# PiZeroRobotHat.net
KiCad netlist of a schematic drawn in EAGLE
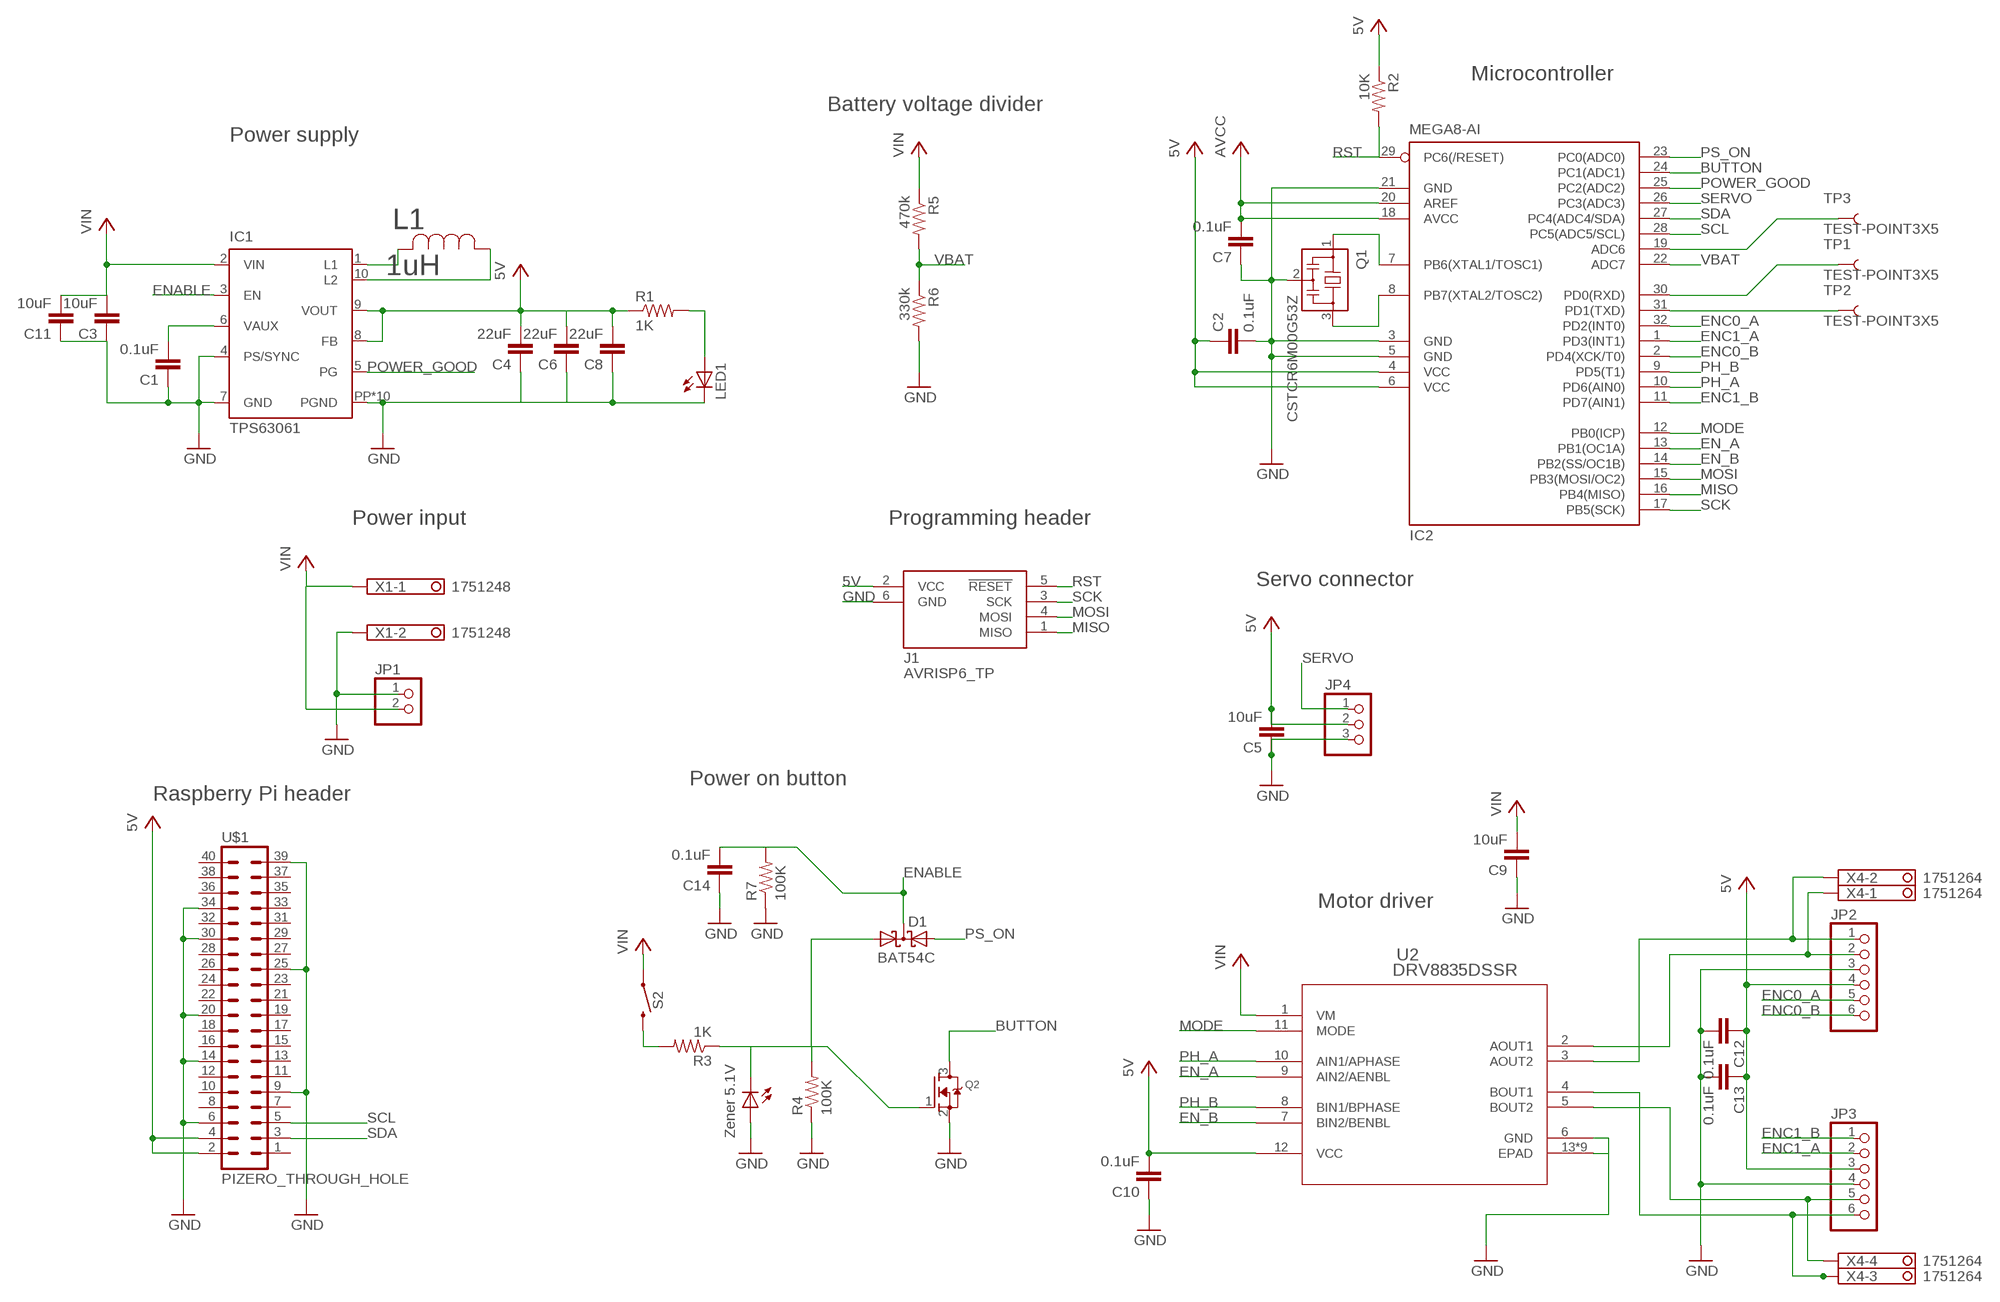
[diagram p0: schematic, sheet 1]

(export (version "E")
  (design (tool "Eeschema 10.0.6"))
  (components
    (comp (ref "C1")
      (value "0.1uF")
      (footprint "eagle-import:C0603K")
      (libsource (lib "eagle-import") (part "C-EUC0603K"))
    )
    (comp (ref "C2")
      (value "0.1uF")
      (footprint "eagle-import:C0603K")
      (libsource (lib "eagle-import") (part "C-EUC0603K"))
    )
    (comp (ref "C3")
      (value "10uF")
      (footprint "eagle-import:C0805K")
      (libsource (lib "eagle-import") (part "C-EUC0805K"))
    )
    (comp (ref "C4")
      (value "22uF")
      (footprint "eagle-import:C0805K")
      (libsource (lib "eagle-import") (part "C-EUC0805K"))
    )
    (comp (ref "C5")
      (value "10uF")
      (footprint "eagle-import:C0805K")
      (libsource (lib "eagle-import") (part "C-EUC0805K"))
    )
    (comp (ref "C6")
      (value "22uF")
      (footprint "eagle-import:C0805K")
      (libsource (lib "eagle-import") (part "C-EUC0805K"))
    )
    (comp (ref "C7")
      (value "0.1uF")
      (footprint "eagle-import:C0603K")
      (libsource (lib "eagle-import") (part "C-EUC0603K"))
    )
    (comp (ref "C8")
      (value "22uF")
      (footprint "eagle-import:C0805K")
      (libsource (lib "eagle-import") (part "C-EUC0805K"))
    )
    (comp (ref "C9")
      (value "10uF")
      (footprint "eagle-import:C0805K")
      (libsource (lib "eagle-import") (part "C-EUC0805K"))
    )
    (comp (ref "C10")
      (value "0.1uF")
      (footprint "eagle-import:C0603K")
      (libsource (lib "eagle-import") (part "C-EUC0603K"))
    )
    (comp (ref "C11")
      (value "10uF")
      (footprint "eagle-import:C0805K")
      (libsource (lib "eagle-import") (part "C-EUC0805K"))
    )
    (comp (ref "C12")
      (value "0.1uF")
      (footprint "eagle-import:C0603K")
      (libsource (lib "eagle-import") (part "C-EUC0603K"))
    )
    (comp (ref "C13")
      (value "0.1uF")
      (footprint "eagle-import:C0603K")
      (libsource (lib "eagle-import") (part "C-EUC0603K"))
    )
    (comp (ref "C14")
      (value "0.1uF")
      (footprint "eagle-import:C0603K")
      (libsource (lib "eagle-import") (part "C-EUC0603K"))
    )
    (comp (ref "D1")
      (value "BAT54C")
      (footprint "eagle-import:SOT23")
      (libsource (lib "eagle-import") (part "BAT54C"))
    )
    (comp (ref "IC1")
      (value "TPS63061")
      (footprint "eagle-import:DSC-S-PWSON-N10")
      (libsource (lib "eagle-import") (part "TPS63061"))
    )
    (comp (ref "IC2")
      (value "MEGA8-AI")
      (footprint "eagle-import:TQFP32-08")
      (fields (field (name "MPN") "ATMEGA8-16AU"))
      (libsource (lib "eagle-import") (part "MEGA8-AI"))
    )
    (comp (ref "J1")
      (value "AVRISP6_TP")
      (footprint "eagle-import:2X3_TP")
      (libsource (lib "eagle-import") (part "AVRISP6_TP"))
    )
    (comp (ref "JP1")
      (value "PINHD-1X2")
      (footprint "eagle-import:1X02")
      (libsource (lib "eagle-import") (part "PINHD-1X2"))
    )
    (comp (ref "JP2")
      (value "PINHD-1X6")
      (footprint "eagle-import:1X06")
      (libsource (lib "eagle-import") (part "PINHD-1X6"))
    )
    (comp (ref "JP3")
      (value "PINHD-1X6")
      (footprint "eagle-import:1X06")
      (libsource (lib "eagle-import") (part "PINHD-1X6"))
    )
    (comp (ref "JP4")
      (value "PINHD-1X3")
      (footprint "eagle-import:1X03")
      (libsource (lib "eagle-import") (part "PINHD-1X3"))
    )
    (comp (ref "L1")
      (value "1uH")
      (footprint "eagle-import:IND_TAIYO_NR3015")
      (fields (field (name "MANUFACTURER_PART_NUMBER") "NR3015T1R0N"))
      (libsource (lib "eagle-import") (part "NR3015T1R0N"))
    )
    (comp (ref "LD1")
      (value "PL006-WCR12")
      (footprint "eagle-import:SOT23")
      (libsource (lib "eagle-import") (part "PL006-WCR12"))
    )
    (comp (ref "LED1")
      (value "LEDCHIPLED_0603")
      (footprint "eagle-import:CHIPLED_0603")
      (libsource (lib "eagle-import") (part "LEDCHIPLED_0603"))
    )
    (comp (ref "Q1")
      (value "CSTCR6M00G53Z")
      (footprint "eagle-import:CSTCR6M")
      (fields (field (name "MPN") "CSTCR6M00G53-R0"))
      (libsource (lib "eagle-import") (part "CSTCR6M00G53Z"))
    )
    (comp (ref "Q2")
      (value "MOSFET-NREFLOW")
      (footprint "eagle-import:SOT23")
      (libsource (lib "eagle-import") (part "MOSFET-NREFLOW"))
    )
    (comp (ref "R1")
      (value "1K")
      (footprint "eagle-import:R0603")
      (libsource (lib "eagle-import") (part "R-US_R0603"))
    )
    (comp (ref "R2")
      (value "10K")
      (footprint "eagle-import:R0603")
      (libsource (lib "eagle-import") (part "resistor_348_R-US_R0603"))
    )
    (comp (ref "R3")
      (value "1K")
      (footprint "eagle-import:R0603")
      (libsource (lib "eagle-import") (part "resistor_348_R-US_R0603"))
    )
    (comp (ref "R4")
      (value "100K")
      (footprint "eagle-import:R0603")
      (libsource (lib "eagle-import") (part "resistor_348_R-US_R0603"))
    )
    (comp (ref "R5")
      (value "470k")
      (footprint "eagle-import:R0603")
      (libsource (lib "eagle-import") (part "R-US_R0603"))
    )
    (comp (ref "R6")
      (value "330k")
      (footprint "eagle-import:R0603")
      (libsource (lib "eagle-import") (part "R-US_R0603"))
    )
    (comp (ref "R7")
      (value "100K")
      (footprint "eagle-import:R0603")
      (libsource (lib "eagle-import") (part "resistor_348_R-US_R0603"))
    )
    (comp (ref "S2")
      (value "MOMENTARY-SWITCH-SPST")
      (footprint "eagle-import:TACTILE_SWITCH_SMD_4X3MM")
      (libsource (lib "eagle-import") (part "MOMENTARY-SWITCH-SPST"))
    )
    (comp (ref "TP1")
      (value "TEST-POINT3X5")
      (footprint "eagle-import:PAD.03X.05")
      (libsource (lib "eagle-import") (part "TEST-POINT3X5"))
    )
    (comp (ref "TP2")
      (value "TEST-POINT3X5")
      (footprint "eagle-import:PAD.03X.05")
      (libsource (lib "eagle-import") (part "TEST-POINT3X5"))
    )
    (comp (ref "TP3")
      (value "TEST-POINT3X5")
      (footprint "eagle-import:PAD.03X.05")
      (libsource (lib "eagle-import") (part "TEST-POINT3X5"))
    )
    (comp (ref "U$1")
      (value "PIZERO_THROUGH_HOLE")
      (footprint "eagle-import:PIZERO_THOUGH_HOLE")
      (libsource (lib "eagle-import") (part "PIZERO_THROUGH_HOLE"))
    )
    (comp (ref "U2")
      (value "DRV8835DSSR")
      (footprint "eagle-import:DSS12_P9X2")
      (fields (field (name "COPYRIGHT") "Copyright C 2015 Accelerated Designs. All rights reserved"))
      (libsource (lib "eagle-import") (part "DRV8835DSSR"))
    )
    (comp (ref "X1")
      (value "1751248")
      (footprint "eagle-import:1751248")
      (libsource (lib "eagle-import") (part "1751248"))
    )
    (comp (ref "X4")
      (value "1751264")
      (footprint "eagle-import:1751264")
      (libsource (lib "eagle-import") (part "1751264"))
    )
  )
  (nets
    (net (code "1") (name "/BUTTON") (class "Default")
      (node (ref "IC2") (pin "24") (pinfunction "PC1(ADC1)_24") (pintype "bidirectional"))
      (node (ref "Q2") (pin "3") (pinfunction "D_3") (pintype "bidirectional"))
    )
    (net (code "2") (name "/ENABLE") (class "Default")
      (node (ref "C14") (pin "2") (pinfunction "2_2") (pintype "passive"))
      (node (ref "D1") (pin "3") (pinfunction "CC_3") (pintype "passive"))
      (node (ref "IC1") (pin "3") (pinfunction "EN_3") (pintype "input"))
      (node (ref "R7") (pin "2") (pinfunction "2_2") (pintype "passive"))
    )
    (net (code "3") (name "/ENC0_A") (class "Default")
      (node (ref "IC2") (pin "32") (pinfunction "PD2(INT0)_32") (pintype "bidirectional"))
      (node (ref "JP2") (pin "5") (pinfunction "5_5") (pintype "passive"))
    )
    (net (code "4") (name "/ENC0_B") (class "Default")
      (node (ref "IC2") (pin "2") (pinfunction "PD4(XCK/T0)_2") (pintype "bidirectional"))
      (node (ref "JP2") (pin "6") (pinfunction "6_6") (pintype "passive"))
    )
    (net (code "5") (name "/ENC1_A") (class "Default")
      (node (ref "IC2") (pin "1") (pinfunction "PD3(INT1)_1") (pintype "bidirectional"))
      (node (ref "JP3") (pin "2") (pinfunction "2_2") (pintype "passive"))
    )
    (net (code "6") (name "/ENC1_B") (class "Default")
      (node (ref "IC2") (pin "11") (pinfunction "PD7(AIN1)_11") (pintype "bidirectional"))
      (node (ref "JP3") (pin "1") (pinfunction "1_1") (pintype "passive"))
    )
    (net (code "7") (name "/EN_A") (class "Default")
      (node (ref "IC2") (pin "13") (pinfunction "PB1(OC1A)_13") (pintype "bidirectional"))
      (node (ref "U2") (pin "9") (pinfunction "AIN2/AENBL_9") (pintype "input"))
    )
    (net (code "8") (name "/EN_B") (class "Default")
      (node (ref "IC2") (pin "14") (pinfunction "PB2(SS/OC1B)_14") (pintype "bidirectional"))
      (node (ref "U2") (pin "7") (pinfunction "BIN2/BENBL_7") (pintype "input"))
    )
    (net (code "9") (name "/MISO") (class "Default")
      (node (ref "IC2") (pin "16") (pinfunction "PB4(MISO)_16") (pintype "bidirectional"))
      (node (ref "J1") (pin "1") (pinfunction "MISO_1") (pintype "input"))
    )
    (net (code "10") (name "/MODE") (class "Default")
      (node (ref "IC2") (pin "12") (pinfunction "PB0(ICP)_12") (pintype "bidirectional"))
      (node (ref "U2") (pin "11") (pinfunction "MODE_11") (pintype "input"))
    )
    (net (code "11") (name "/MOSI") (class "Default")
      (node (ref "IC2") (pin "15") (pinfunction "PB3(MOSI/OC2)_15") (pintype "bidirectional"))
      (node (ref "J1") (pin "4") (pinfunction "MOSI_4") (pintype "output"))
    )
    (net (code "12") (name "/PH_A") (class "Default")
      (node (ref "IC2") (pin "10") (pinfunction "PD6(AIN0)_10") (pintype "bidirectional"))
      (node (ref "U2") (pin "10") (pinfunction "AIN1/APHASE_10") (pintype "input"))
    )
    (net (code "13") (name "/PH_B") (class "Default")
      (node (ref "IC2") (pin "9") (pinfunction "PD5(T1)_9") (pintype "bidirectional"))
      (node (ref "U2") (pin "8") (pinfunction "BIN1/BPHASE_8") (pintype "input"))
    )
    (net (code "14") (name "/POWER_GOOD") (class "Default")
      (node (ref "IC1") (pin "5") (pinfunction "PG_5") (pintype "output"))
      (node (ref "IC2") (pin "25") (pinfunction "PC2(ADC2)_25") (pintype "bidirectional"))
    )
    (net (code "15") (name "/PS_ON") (class "Default")
      (node (ref "D1") (pin "2") (pinfunction "A2_2") (pintype "passive"))
      (node (ref "IC2") (pin "23") (pinfunction "PC0(ADC0)_23") (pintype "bidirectional"))
    )
    (net (code "16") (name "/RST") (class "Default")
      (node (ref "IC2") (pin "29") (pinfunction "PC6(/RESET)_29") (pintype "bidirectional"))
      (node (ref "J1") (pin "5") (pinfunction "~{RESET}_5") (pintype "output"))
      (node (ref "R2") (pin "2") (pinfunction "2_2") (pintype "passive"))
    )
    (net (code "17") (name "/SCK") (class "Default")
      (node (ref "IC2") (pin "17") (pinfunction "PB5(SCK)_17") (pintype "bidirectional"))
      (node (ref "J1") (pin "3") (pinfunction "SCK_3") (pintype "output"))
    )
    (net (code "18") (name "/SCL") (class "Default")
      (node (ref "IC2") (pin "28") (pinfunction "PC5(ADC5/SCL)_28") (pintype "bidirectional"))
      (node (ref "U$1") (pin "5") (pinfunction "5_5") (pintype "passive"))
    )
    (net (code "19") (name "/SDA") (class "Default")
      (node (ref "IC2") (pin "27") (pinfunction "PC4(ADC4/SDA)_27") (pintype "bidirectional"))
      (node (ref "U$1") (pin "3") (pinfunction "3_3") (pintype "passive"))
    )
    (net (code "20") (name "/SERVO") (class "Default")
      (node (ref "IC2") (pin "26") (pinfunction "PC3(ADC3)_26") (pintype "bidirectional"))
      (node (ref "JP4") (pin "1") (pinfunction "1_1") (pintype "passive"))
    )
    (net (code "21") (name "/VBAT") (class "Default")
      (node (ref "IC2") (pin "22") (pinfunction "ADC7_22") (pintype "bidirectional"))
      (node (ref "R5") (pin "2") (pinfunction "2_2") (pintype "passive"))
      (node (ref "R6") (pin "1") (pinfunction "1_1") (pintype "passive"))
    )
    (net (code "22") (name "5V") (class "Default")
      (node (ref "C10") (pin "2") (pinfunction "2_2") (pintype "passive"))
      (node (ref "C12") (pin "1") (pinfunction "1_1") (pintype "passive"))
      (node (ref "C13") (pin "1") (pinfunction "1_1") (pintype "passive"))
      (node (ref "C2") (pin "1") (pinfunction "1_1") (pintype "passive"))
      (node (ref "C4") (pin "2") (pinfunction "2_2") (pintype "passive"))
      (node (ref "C5") (pin "2") (pinfunction "2_2") (pintype "passive"))
      (node (ref "C6") (pin "2") (pinfunction "2_2") (pintype "passive"))
      (node (ref "C7") (pin "2") (pinfunction "2_2") (pintype "passive"))
      (node (ref "C8") (pin "2") (pinfunction "2_2") (pintype "passive"))
      (node (ref "IC1") (pin "8") (pinfunction "FB_8") (pintype "input"))
      (node (ref "IC1") (pin "9") (pinfunction "VOUT_9") (pintype "output"))
      (node (ref "IC2") (pin "18") (pinfunction "AVCC_18") (pintype "power_in"))
      (node (ref "IC2") (pin "20") (pinfunction "AREF_20") (pintype "passive"))
      (node (ref "IC2") (pin "4") (pinfunction "VCC_4") (pintype "power_in"))
      (node (ref "IC2") (pin "6") (pinfunction "VCC_6") (pintype "power_in"))
      (node (ref "J1") (pin "2") (pinfunction "VCC_2") (pintype "power_in"))
      (node (ref "JP2") (pin "4") (pinfunction "4_4") (pintype "passive"))
      (node (ref "JP3") (pin "3") (pinfunction "3_3") (pintype "passive"))
      (node (ref "JP4") (pin "2") (pinfunction "2_2") (pintype "passive"))
      (node (ref "R1") (pin "1") (pinfunction "1_1") (pintype "passive"))
      (node (ref "R2") (pin "1") (pinfunction "1_1") (pintype "passive"))
      (node (ref "U$1") (pin "2") (pinfunction "2_2") (pintype "passive"))
      (node (ref "U$1") (pin "4") (pinfunction "4_4") (pintype "passive"))
      (node (ref "U2") (pin "12") (pinfunction "VCC_12") (pintype "power_in"))
    )
    (net (code "23") (name "GND") (class "Default")
      (node (ref "C1") (pin "1") (pinfunction "1_1") (pintype "passive"))
      (node (ref "C10") (pin "1") (pinfunction "1_1") (pintype "passive"))
      (node (ref "C11") (pin "1") (pinfunction "1_1") (pintype "passive"))
      (node (ref "C12") (pin "2") (pinfunction "2_2") (pintype "passive"))
      (node (ref "C13") (pin "2") (pinfunction "2_2") (pintype "passive"))
      (node (ref "C14") (pin "1") (pinfunction "1_1") (pintype "passive"))
      (node (ref "C2") (pin "2") (pinfunction "2_2") (pintype "passive"))
      (node (ref "C3") (pin "1") (pinfunction "1_1") (pintype "passive"))
      (node (ref "C4") (pin "1") (pinfunction "1_1") (pintype "passive"))
      (node (ref "C5") (pin "1") (pinfunction "1_1") (pintype "passive"))
      (node (ref "C6") (pin "1") (pinfunction "1_1") (pintype "passive"))
      (node (ref "C7") (pin "1") (pinfunction "1_1") (pintype "passive"))
      (node (ref "C8") (pin "1") (pinfunction "1_1") (pintype "passive"))
      (node (ref "C9") (pin "1") (pinfunction "1_1") (pintype "passive"))
      (node (ref "IC1") (pin "4") (pinfunction "PS/SYNC_4") (pintype "input"))
      (node (ref "IC1") (pin "7") (pinfunction "GND_7") (pintype "input"))
      (node (ref "IC1") (pin "PP") (pinfunction "PGND_PP") (pintype "power_in"))
      (node (ref "IC1") (pin "PP@1") (pinfunction "PGND_PP@1") (pintype "power_in"))
      (node (ref "IC1") (pin "PP@10") (pinfunction "PGND_PP@10") (pintype "power_in"))
      (node (ref "IC1") (pin "PP@2") (pinfunction "PGND_PP@2") (pintype "power_in"))
      (node (ref "IC1") (pin "PP@3") (pinfunction "PGND_PP@3") (pintype "power_in"))
      (node (ref "IC1") (pin "PP@4") (pinfunction "PGND_PP@4") (pintype "power_in"))
      (node (ref "IC1") (pin "PP@5") (pinfunction "PGND_PP@5") (pintype "power_in"))
      (node (ref "IC1") (pin "PP@7") (pinfunction "PGND_PP@7") (pintype "power_in"))
      (node (ref "IC1") (pin "PP@8") (pinfunction "PGND_PP@8") (pintype "power_in"))
      (node (ref "IC1") (pin "PP@9") (pinfunction "PGND_PP@9") (pintype "power_in"))
      (node (ref "IC2") (pin "21") (pinfunction "GND_21") (pintype "power_in"))
      (node (ref "IC2") (pin "3") (pinfunction "GND_3") (pintype "power_in"))
      (node (ref "IC2") (pin "5") (pinfunction "GND_5") (pintype "power_in"))
      (node (ref "J1") (pin "6") (pinfunction "GND_6") (pintype "power_in"))
      (node (ref "JP1") (pin "1") (pinfunction "1_1") (pintype "passive"))
      (node (ref "JP2") (pin "3") (pinfunction "3_3") (pintype "passive"))
      (node (ref "JP3") (pin "4") (pinfunction "4_4") (pintype "passive"))
      (node (ref "JP4") (pin "3") (pinfunction "3_3") (pintype "passive"))
      (node (ref "LD1") (pin "1") (pinfunction "A_1") (pintype "passive"))
      (node (ref "LED1") (pin "C") (pinfunction "C_C") (pintype "passive"))
      (node (ref "Q1") (pin "2") (pinfunction "2_2") (pintype "passive"))
      (node (ref "Q2") (pin "2") (pinfunction "S_2") (pintype "bidirectional"))
      (node (ref "R4") (pin "1") (pinfunction "1_1") (pintype "passive"))
      (node (ref "R6") (pin "2") (pinfunction "2_2") (pintype "passive"))
      (node (ref "R7") (pin "1") (pinfunction "1_1") (pintype "passive"))
      (node (ref "U$1") (pin "14") (pinfunction "14_14") (pintype "passive"))
      (node (ref "U$1") (pin "20") (pinfunction "20_20") (pintype "passive"))
      (node (ref "U$1") (pin "25") (pinfunction "25_25") (pintype "passive"))
      (node (ref "U$1") (pin "30") (pinfunction "30_30") (pintype "passive"))
      (node (ref "U$1") (pin "34") (pinfunction "34_34") (pintype "passive"))
      (node (ref "U$1") (pin "39") (pinfunction "39_39") (pintype "passive"))
      (node (ref "U$1") (pin "6") (pinfunction "6_6") (pintype "passive"))
      (node (ref "U$1") (pin "9") (pinfunction "9_9") (pintype "passive"))
      (node (ref "U2") (pin "13") (pinfunction "EPAD_13") (pintype "passive"))
      (node (ref "U2") (pin "14") (pinfunction "EPAD_14") (pintype "passive"))
      (node (ref "U2") (pin "15") (pinfunction "EPAD_15") (pintype "passive"))
      (node (ref "U2") (pin "16") (pinfunction "EPAD_16") (pintype "passive"))
      (node (ref "U2") (pin "17") (pinfunction "EPAD_17") (pintype "passive"))
      (node (ref "U2") (pin "18") (pinfunction "EPAD_18") (pintype "passive"))
      (node (ref "U2") (pin "6") (pinfunction "GND_6") (pintype "power_in"))
      (node (ref "U2") (pin "P$1") (pinfunction "EPAD_P$1") (pintype "passive"))
      (node (ref "U2") (pin "P$2") (pinfunction "EPAD_P$2") (pintype "passive"))
      (node (ref "U2") (pin "P$3") (pinfunction "EPAD_P$3") (pintype "passive"))
      (node (ref "X1") (pin "2") (pinfunction "K_2") (pintype "passive"))
    )
    (net (code "24") (name "Net-(D1-A1)") (class "Default")
      (node (ref "D1") (pin "1") (pinfunction "A1_1") (pintype "passive"))
      (node (ref "LD1") (pin "3") (pinfunction "C_3") (pintype "passive"))
      (node (ref "Q2") (pin "1") (pinfunction "G_1") (pintype "bidirectional"))
      (node (ref "R3") (pin "1") (pinfunction "1_1") (pintype "passive"))
      (node (ref "R4") (pin "2") (pinfunction "2_2") (pintype "passive"))
    )
    (net (code "25") (name "Net-(IC1-L1)") (class "Default")
      (node (ref "IC1") (pin "1") (pinfunction "L1_1") (pintype "input"))
      (node (ref "L1") (pin "2") (pinfunction "2_2") (pintype "passive"))
    )
    (net (code "26") (name "Net-(IC1-L2)") (class "Default")
      (node (ref "IC1") (pin "10") (pinfunction "L2_10") (pintype "input"))
      (node (ref "L1") (pin "1") (pinfunction "1_1") (pintype "passive"))
    )
    (net (code "27") (name "Net-(IC1-VAUX)") (class "Default")
      (node (ref "C1") (pin "2") (pinfunction "2_2") (pintype "passive"))
      (node (ref "IC1") (pin "6") (pinfunction "VAUX_6") (pintype "power_in"))
    )
    (net (code "28") (name "Net-(IC2-ADC6)") (class "Default")
      (node (ref "IC2") (pin "19") (pinfunction "ADC6_19") (pintype "bidirectional"))
      (node (ref "TP3") (pin "P$1") (pinfunction "1_P$1") (pintype "bidirectional"))
    )
    (net (code "29") (name "Net-(IC2-PB6(XTAL1{slash}TOSC1))") (class "Default")
      (node (ref "IC2") (pin "7") (pinfunction "PB6(XTAL1/TOSC1)_7") (pintype "bidirectional"))
      (node (ref "Q1") (pin "1") (pinfunction "1_1") (pintype "passive"))
    )
    (net (code "30") (name "Net-(IC2-PB7(XTAL2{slash}TOSC2))") (class "Default")
      (node (ref "IC2") (pin "8") (pinfunction "PB7(XTAL2/TOSC2)_8") (pintype "bidirectional"))
      (node (ref "Q1") (pin "3") (pinfunction "3_3") (pintype "passive"))
    )
    (net (code "31") (name "Net-(IC2-PD0(RXD))") (class "Default")
      (node (ref "IC2") (pin "30") (pinfunction "PD0(RXD)_30") (pintype "bidirectional"))
      (node (ref "TP1") (pin "P$1") (pinfunction "1_P$1") (pintype "bidirectional"))
    )
    (net (code "32") (name "Net-(IC2-PD1(TXD))") (class "Default")
      (node (ref "IC2") (pin "31") (pinfunction "PD1(TXD)_31") (pintype "bidirectional"))
      (node (ref "TP2") (pin "P$1") (pinfunction "1_P$1") (pintype "bidirectional"))
    )
    (net (code "33") (name "Net-(LED1-PadA)") (class "Default")
      (node (ref "LED1") (pin "A") (pinfunction "A_A") (pintype "passive"))
      (node (ref "R1") (pin "2") (pinfunction "2_2") (pintype "passive"))
    )
    (net (code "34") (name "Net-(R3-Pad2)") (class "Default")
      (node (ref "R3") (pin "2") (pinfunction "2_2") (pintype "passive"))
      (node (ref "S2") (pin "2") (pinfunction "2_2") (pintype "passive"))
    )
    (net (code "35") (name "Net-(U2-AOUT1)") (class "Default")
      (node (ref "JP2") (pin "2") (pinfunction "2_2") (pintype "passive"))
      (node (ref "U2") (pin "2") (pinfunction "AOUT1_2") (pintype "output"))
      (node (ref "X4") (pin "1") (pinfunction "K_1") (pintype "passive"))
    )
    (net (code "36") (name "Net-(U2-AOUT2)") (class "Default")
      (node (ref "JP2") (pin "1") (pinfunction "1_1") (pintype "passive"))
      (node (ref "U2") (pin "3") (pinfunction "AOUT2_3") (pintype "output"))
      (node (ref "X4") (pin "2") (pinfunction "K_2") (pintype "passive"))
    )
    (net (code "37") (name "Net-(U2-BOUT1)") (class "Default")
      (node (ref "JP3") (pin "6") (pinfunction "6_6") (pintype "passive"))
      (node (ref "U2") (pin "4") (pinfunction "BOUT1_4") (pintype "output"))
      (node (ref "X4") (pin "3") (pinfunction "K_3") (pintype "passive"))
    )
    (net (code "38") (name "Net-(U2-BOUT2)") (class "Default")
      (node (ref "JP3") (pin "5") (pinfunction "5_5") (pintype "passive"))
      (node (ref "U2") (pin "5") (pinfunction "BOUT2_5") (pintype "output"))
      (node (ref "X4") (pin "4") (pinfunction "K_4") (pintype "passive"))
    )
    (net (code "39") (name "VIN") (class "Default")
      (node (ref "C11") (pin "2") (pinfunction "2_2") (pintype "passive"))
      (node (ref "C3") (pin "2") (pinfunction "2_2") (pintype "passive"))
      (node (ref "C9") (pin "2") (pinfunction "2_2") (pintype "passive"))
      (node (ref "IC1") (pin "2") (pinfunction "VIN_2") (pintype "input"))
      (node (ref "JP1") (pin "2") (pinfunction "2_2") (pintype "passive"))
      (node (ref "R5") (pin "1") (pinfunction "1_1") (pintype "passive"))
      (node (ref "S2") (pin "1") (pinfunction "1_1") (pintype "passive"))
      (node (ref "U2") (pin "1") (pinfunction "VM_1") (pintype "power_in"))
      (node (ref "X1") (pin "1") (pinfunction "K_1") (pintype "passive"))
    )
    (net (code "40") (name "unconnected-(U$1-Pad1)") (class "Default")
      (node (ref "U$1") (pin "1") (pinfunction "1_1") (pintype "passive"))
    )
    (net (code "41") (name "unconnected-(U$1-Pad7)") (class "Default")
      (node (ref "U$1") (pin "7") (pinfunction "7_7") (pintype "passive"))
    )
    (net (code "42") (name "unconnected-(U$1-Pad8)") (class "Default")
      (node (ref "U$1") (pin "8") (pinfunction "8_8") (pintype "passive"))
    )
    (net (code "43") (name "unconnected-(U$1-Pad10)") (class "Default")
      (node (ref "U$1") (pin "10") (pinfunction "10_10") (pintype "passive"))
    )
    (net (code "44") (name "unconnected-(U$1-Pad11)") (class "Default")
      (node (ref "U$1") (pin "11") (pinfunction "11_11") (pintype "passive"))
    )
    (net (code "45") (name "unconnected-(U$1-Pad12)") (class "Default")
      (node (ref "U$1") (pin "12") (pinfunction "12_12") (pintype "passive"))
    )
    (net (code "46") (name "unconnected-(U$1-Pad13)") (class "Default")
      (node (ref "U$1") (pin "13") (pinfunction "13_13") (pintype "passive"))
    )
    (net (code "47") (name "unconnected-(U$1-Pad15)") (class "Default")
      (node (ref "U$1") (pin "15") (pinfunction "15_15") (pintype "passive"))
    )
    (net (code "48") (name "unconnected-(U$1-Pad16)") (class "Default")
      (node (ref "U$1") (pin "16") (pinfunction "16_16") (pintype "passive"))
    )
    (net (code "49") (name "unconnected-(U$1-Pad17)") (class "Default")
      (node (ref "U$1") (pin "17") (pinfunction "17_17") (pintype "passive"))
    )
    (net (code "50") (name "unconnected-(U$1-Pad18)") (class "Default")
      (node (ref "U$1") (pin "18") (pinfunction "18_18") (pintype "passive"))
    )
    (net (code "51") (name "unconnected-(U$1-Pad19)") (class "Default")
      (node (ref "U$1") (pin "19") (pinfunction "19_19") (pintype "passive"))
    )
    (net (code "52") (name "unconnected-(U$1-Pad21)") (class "Default")
      (node (ref "U$1") (pin "21") (pinfunction "21_21") (pintype "passive"))
    )
    (net (code "53") (name "unconnected-(U$1-Pad22)") (class "Default")
      (node (ref "U$1") (pin "22") (pinfunction "22_22") (pintype "passive"))
    )
    (net (code "54") (name "unconnected-(U$1-Pad23)") (class "Default")
      (node (ref "U$1") (pin "23") (pinfunction "23_23") (pintype "passive"))
    )
    (net (code "55") (name "unconnected-(U$1-Pad24)") (class "Default")
      (node (ref "U$1") (pin "24") (pinfunction "24_24") (pintype "passive"))
    )
    (net (code "56") (name "unconnected-(U$1-Pad26)") (class "Default")
      (node (ref "U$1") (pin "26") (pinfunction "26_26") (pintype "passive"))
    )
    (net (code "57") (name "unconnected-(U$1-Pad27)") (class "Default")
      (node (ref "U$1") (pin "27") (pinfunction "27_27") (pintype "passive"))
    )
    (net (code "58") (name "unconnected-(U$1-Pad28)") (class "Default")
      (node (ref "U$1") (pin "28") (pinfunction "28_28") (pintype "passive"))
    )
    (net (code "59") (name "unconnected-(U$1-Pad29)") (class "Default")
      (node (ref "U$1") (pin "29") (pinfunction "29_29") (pintype "passive"))
    )
    (net (code "60") (name "unconnected-(U$1-Pad31)") (class "Default")
      (node (ref "U$1") (pin "31") (pinfunction "31_31") (pintype "passive"))
    )
    (net (code "61") (name "unconnected-(U$1-Pad32)") (class "Default")
      (node (ref "U$1") (pin "32") (pinfunction "32_32") (pintype "passive"))
    )
    (net (code "62") (name "unconnected-(U$1-Pad33)") (class "Default")
      (node (ref "U$1") (pin "33") (pinfunction "33_33") (pintype "passive"))
    )
    (net (code "63") (name "unconnected-(U$1-Pad35)") (class "Default")
      (node (ref "U$1") (pin "35") (pinfunction "35_35") (pintype "passive"))
    )
    (net (code "64") (name "unconnected-(U$1-Pad36)") (class "Default")
      (node (ref "U$1") (pin "36") (pinfunction "36_36") (pintype "passive"))
    )
    (net (code "65") (name "unconnected-(U$1-Pad37)") (class "Default")
      (node (ref "U$1") (pin "37") (pinfunction "37_37") (pintype "passive"))
    )
    (net (code "66") (name "unconnected-(U$1-Pad38)") (class "Default")
      (node (ref "U$1") (pin "38") (pinfunction "38_38") (pintype "passive"))
    )
    (net (code "67") (name "unconnected-(U$1-Pad40)") (class "Default")
      (node (ref "U$1") (pin "40") (pinfunction "40_40") (pintype "passive"))
    )
  )
)
